# lf.net
KiCad netlist of a schematic drawn in EAGLE
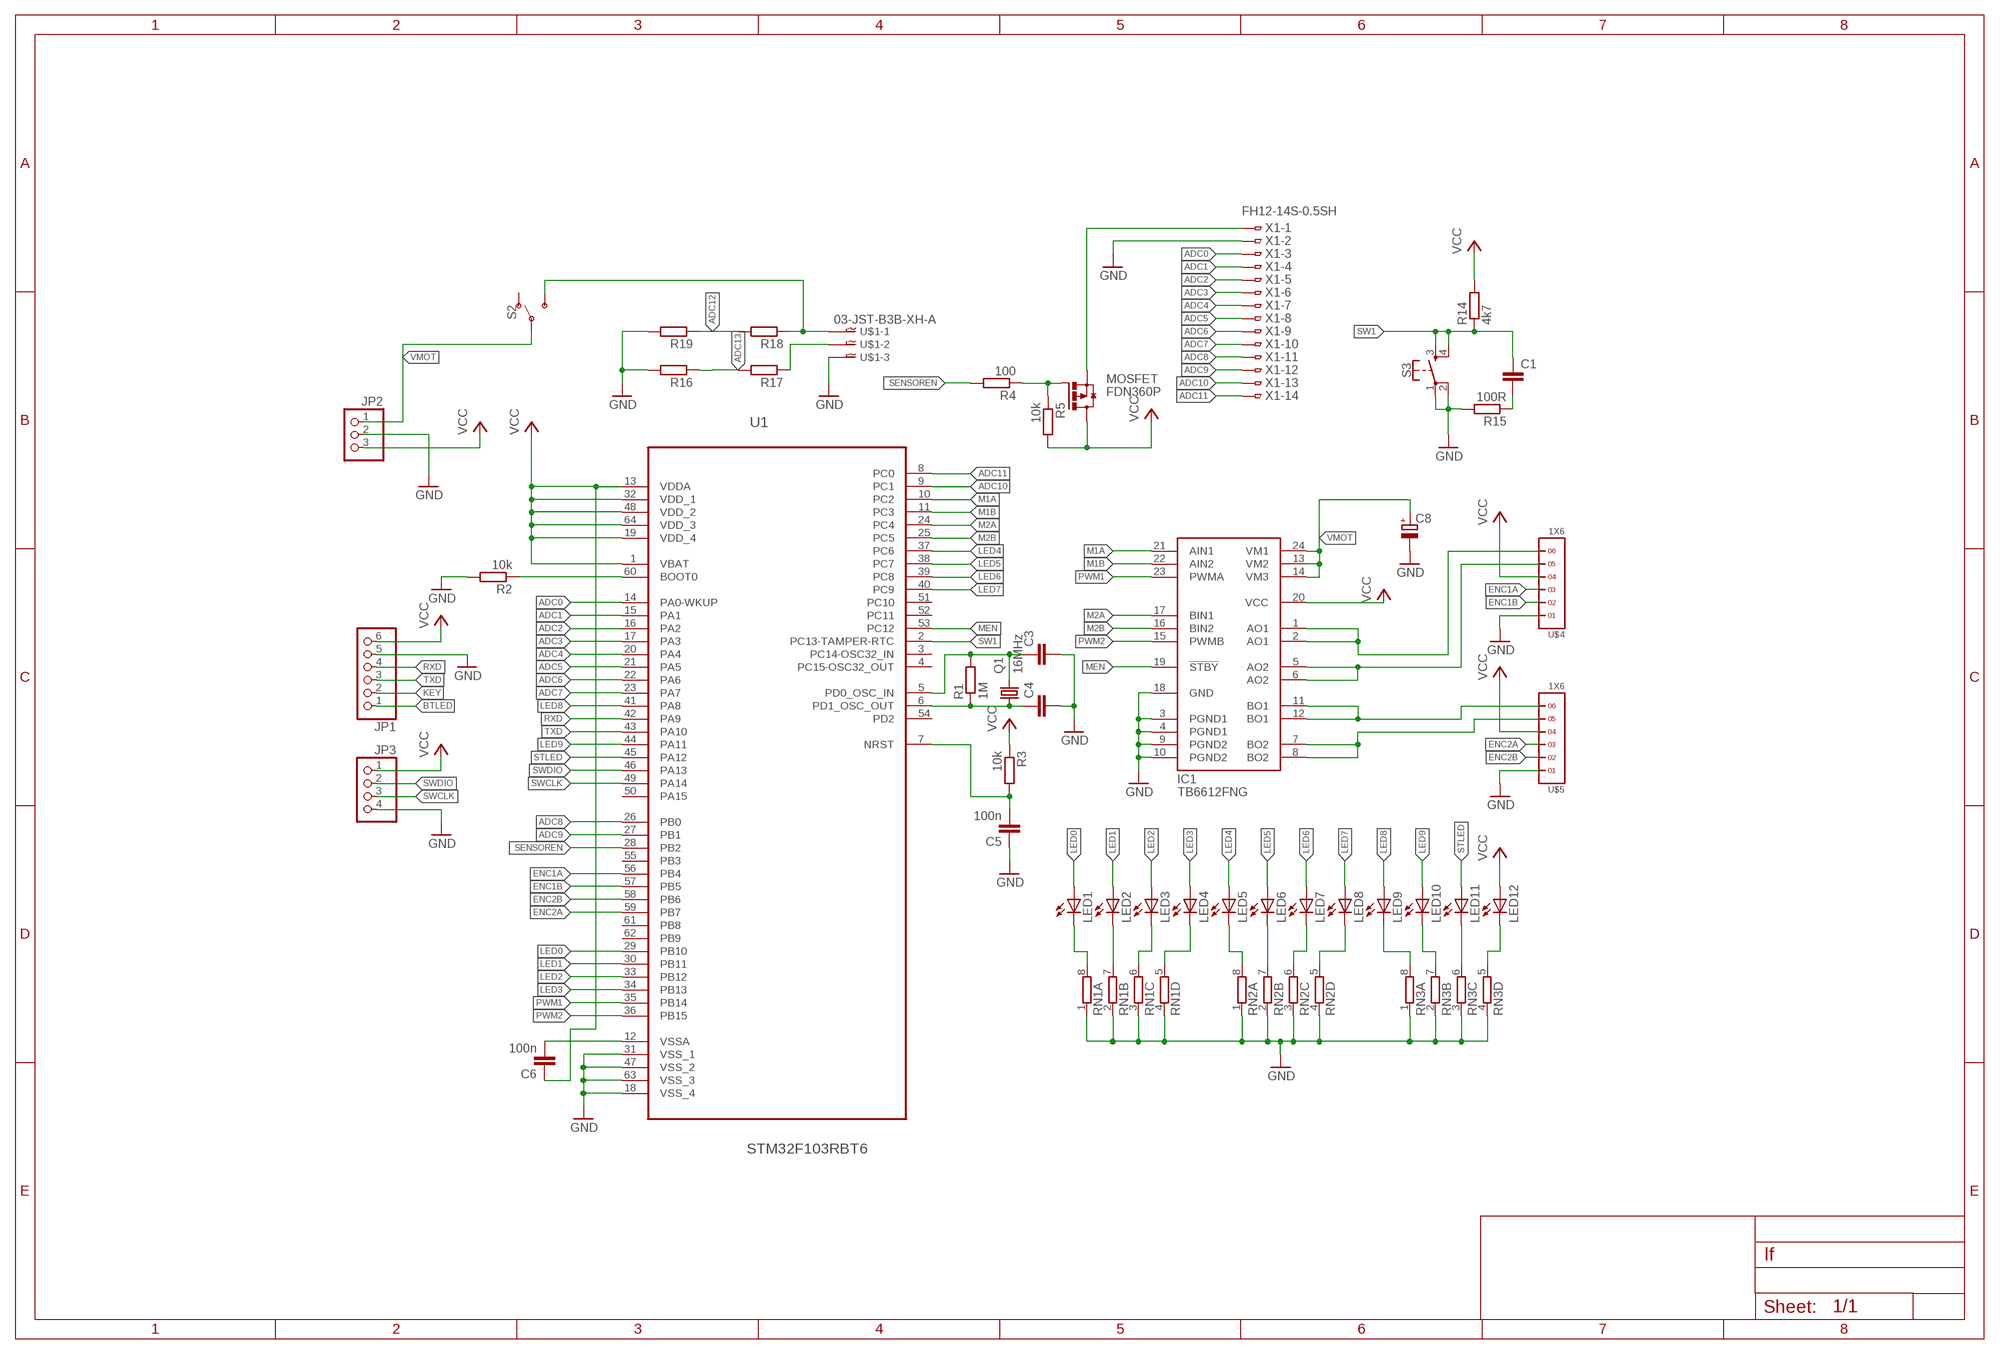
[diagram p0: schematic, sheet 1]

(export (version "E")
  (design (tool "Eeschema 10.0.6"))
  (components
    (comp (ref "C1")
      (value "C-EUC0603K")
      (footprint "eagle-import:C0603K")
      (libsource (lib "eagle-import") (part "C-EUC0603K"))
    )
    (comp (ref "C3")
      (value "C-EUC0603K")
      (footprint "eagle-import:C0603K")
      (libsource (lib "eagle-import") (part "C-EUC0603K"))
    )
    (comp (ref "C4")
      (value "C-EUC0603K")
      (footprint "eagle-import:C0603K")
      (libsource (lib "eagle-import") (part "C-EUC0603K"))
    )
    (comp (ref "C5")
      (value "100n")
      (footprint "eagle-import:C0603K")
      (libsource (lib "eagle-import") (part "C-EUC0603K"))
    )
    (comp (ref "C6")
      (value "100n")
      (footprint "eagle-import:C0603K")
      (libsource (lib "eagle-import") (part "C-EUC0603K"))
    )
    (comp (ref "C8")
      (value "CPOL-EUC/6032-28R")
      (footprint "eagle-import:C_6032-28R")
      (libsource (lib "eagle-import") (part "CPOL-EUC/6032-28R"))
    )
    (comp (ref "IC1")
      (value "TB6612FNG")
      (footprint "eagle-import:SSOP24")
      (libsource (lib "eagle-import") (part "TB6612FNG"))
    )
    (comp (ref "JP1")
      (value "PINHD-1X6")
      (footprint "eagle-import:1X06")
      (libsource (lib "eagle-import") (part "PINHD-1X6"))
    )
    (comp (ref "JP2")
      (value "PINHD-1X3")
      (footprint "eagle-import:1X03")
      (libsource (lib "eagle-import") (part "PINHD-1X3"))
    )
    (comp (ref "JP3")
      (value "PINHD-1X4")
      (footprint "eagle-import:1X04")
      (libsource (lib "eagle-import") (part "PINHD-1X4"))
    )
    (comp (ref "LED1")
      (value "LEDCHIPLED_0603")
      (footprint "eagle-import:CHIPLED_0603")
      (libsource (lib "eagle-import") (part "LEDCHIPLED_0603"))
    )
    (comp (ref "LED2")
      (value "LEDCHIPLED_0603")
      (footprint "eagle-import:CHIPLED_0603")
      (libsource (lib "eagle-import") (part "LEDCHIPLED_0603"))
    )
    (comp (ref "LED3")
      (value "LEDCHIPLED_0603")
      (footprint "eagle-import:CHIPLED_0603")
      (libsource (lib "eagle-import") (part "LEDCHIPLED_0603"))
    )
    (comp (ref "LED4")
      (value "LEDCHIPLED_0603")
      (footprint "eagle-import:CHIPLED_0603")
      (libsource (lib "eagle-import") (part "LEDCHIPLED_0603"))
    )
    (comp (ref "LED5")
      (value "LEDCHIPLED_0603")
      (footprint "eagle-import:CHIPLED_0603")
      (libsource (lib "eagle-import") (part "LEDCHIPLED_0603"))
    )
    (comp (ref "LED6")
      (value "LEDCHIPLED_0603")
      (footprint "eagle-import:CHIPLED_0603")
      (libsource (lib "eagle-import") (part "LEDCHIPLED_0603"))
    )
    (comp (ref "LED7")
      (value "LEDCHIPLED_0603")
      (footprint "eagle-import:CHIPLED_0603")
      (libsource (lib "eagle-import") (part "LEDCHIPLED_0603"))
    )
    (comp (ref "LED8")
      (value "LEDCHIPLED_0603")
      (footprint "eagle-import:CHIPLED_0603")
      (libsource (lib "eagle-import") (part "LEDCHIPLED_0603"))
    )
    (comp (ref "LED9")
      (value "LEDCHIPLED_0603")
      (footprint "eagle-import:CHIPLED_0603")
      (libsource (lib "eagle-import") (part "LEDCHIPLED_0603"))
    )
    (comp (ref "LED10")
      (value "LEDCHIPLED_0603")
      (footprint "eagle-import:CHIPLED_0603")
      (libsource (lib "eagle-import") (part "LEDCHIPLED_0603"))
    )
    (comp (ref "LED11")
      (value "LEDCHIPLED_0603")
      (footprint "eagle-import:CHIPLED_0603")
      (libsource (lib "eagle-import") (part "LEDCHIPLED_0603"))
    )
    (comp (ref "LED12")
      (value "LEDCHIPLED_0603")
      (footprint "eagle-import:CHIPLED_0603")
      (libsource (lib "eagle-import") (part "LEDCHIPLED_0603"))
    )
    (comp (ref "MOSFET")
      (value "FDN360P")
      (footprint "eagle-import:SUPER-SOT3")
      (libsource (lib "eagle-import") (part "FDN360P"))
    )
    (comp (ref "Q1")
      (value "16MHz")
      (footprint "eagle-import:3.2X2.5_KX-7")
      (libsource (lib "eagle-import") (part "KX-7"))
    )
    (comp (ref "R1")
      (value "1M")
      (footprint "eagle-import:R0603")
      (libsource (lib "eagle-import") (part "R-EU_R0603"))
    )
    (comp (ref "R2")
      (value "10k")
      (footprint "eagle-import:R0603")
      (libsource (lib "eagle-import") (part "R-EU_R0603"))
    )
    (comp (ref "R3")
      (value "10k")
      (footprint "eagle-import:R0603")
      (libsource (lib "eagle-import") (part "R-EU_R0603"))
    )
    (comp (ref "R4")
      (value "100")
      (footprint "eagle-import:R0603")
      (libsource (lib "eagle-import") (part "R-EU_R0603"))
    )
    (comp (ref "R5")
      (value "10k")
      (footprint "eagle-import:R0603")
      (libsource (lib "eagle-import") (part "R-EU_R0603"))
    )
    (comp (ref "R14")
      (value "4k7")
      (footprint "eagle-import:R0603")
      (libsource (lib "eagle-import") (part "R-EU_R0603"))
    )
    (comp (ref "R15")
      (value "100R")
      (footprint "eagle-import:R0603")
      (libsource (lib "eagle-import") (part "R-EU_R0603"))
    )
    (comp (ref "R16")
      (value "R-EU_R0603")
      (footprint "eagle-import:R0603")
      (libsource (lib "eagle-import") (part "R-EU_R0603"))
    )
    (comp (ref "R17")
      (value "R-EU_R0603")
      (footprint "eagle-import:R0603")
      (libsource (lib "eagle-import") (part "R-EU_R0603"))
    )
    (comp (ref "R18")
      (value "R-EU_R0603")
      (footprint "eagle-import:R0603")
      (libsource (lib "eagle-import") (part "R-EU_R0603"))
    )
    (comp (ref "R19")
      (value "R-EU_R0603")
      (footprint "eagle-import:R0603")
      (libsource (lib "eagle-import") (part "R-EU_R0603"))
    )
    (comp (ref "RN1")
      (value "4R-NEXB28V")
      (footprint "eagle-import:EXB28V")
      (libsource (lib "eagle-import") (part "4R-NEXB28V"))
    )
    (comp (ref "RN2")
      (value "4R-NEXB28V")
      (footprint "eagle-import:EXB28V")
      (libsource (lib "eagle-import") (part "4R-NEXB28V"))
    )
    (comp (ref "RN3")
      (value "4R-NEXB28V")
      (footprint "eagle-import:EXB28V")
      (libsource (lib "eagle-import") (part "4R-NEXB28V"))
    )
    (comp (ref "S2")
      (value "SWITCH-SPDT-PTH-11.6X4.0MM")
      (footprint "eagle-import:SWITCH_SPDT_PTH_11.6X4.0MM")
      (libsource (lib "eagle-import") (part "SWITCH-SPDT-PTH-11.6X4.0MM"))
    )
    (comp (ref "S3")
      (value "MOMENTARY-SWITCH-SPST-2-SMD-5.2MM")
      (footprint "eagle-import:TACTILE_SWITCH_SMD_5.2MM")
      (libsource (lib "eagle-import") (part "MOMENTARY-SWITCH-SPST-2-SMD-5.2MM"))
    )
    (comp (ref "U$1")
      (value "03-JST-B3B-XH-A")
      (footprint "eagle-import:B3B-XH")
      (libsource (lib "eagle-import") (part "03-JST-B3B-XH-A"))
    )
    (comp (ref "U$4")
      (value "1X6")
      (footprint "eagle-import:1X6")
      (libsource (lib "eagle-import") (part "1X6"))
    )
    (comp (ref "U$5")
      (value "1X6")
      (footprint "eagle-import:1X6")
      (libsource (lib "eagle-import") (part "1X6"))
    )
    (comp (ref "U1")
      (value "STM32F103RBT6")
      (footprint "eagle-import:QFP50P1200X1200X160-64N")
      (fields (field (name "MF") "STMicroelectronics"))
      (libsource (lib "eagle-import") (part "STM32F103RBT6"))
    )
    (comp (ref "X1")
      (value "FH12-14S-0.5SH")
      (footprint "eagle-import:FH12-14S-0.5SH")
      (fields (field (name "MPN") "MC34827"))
      (libsource (lib "eagle-import") (part "FH12-14S-0.5SH"))
    )
  )
  (nets
    (net (code "1") (name "ADC0") (class "Default")
      (node (ref "U1") (pin "14") (pinfunction "PA0-WKUP_14") (pintype "bidirectional"))
      (node (ref "X1") (pin "3") (pinfunction "1_3") (pintype "passive"))
    )
    (net (code "2") (name "ADC1") (class "Default")
      (node (ref "U1") (pin "15") (pinfunction "PA1_15") (pintype "bidirectional"))
      (node (ref "X1") (pin "4") (pinfunction "1_4") (pintype "passive"))
    )
    (net (code "3") (name "ADC2") (class "Default")
      (node (ref "U1") (pin "16") (pinfunction "PA2_16") (pintype "bidirectional"))
      (node (ref "X1") (pin "5") (pinfunction "1_5") (pintype "passive"))
    )
    (net (code "4") (name "ADC3") (class "Default")
      (node (ref "U1") (pin "17") (pinfunction "PA3_17") (pintype "bidirectional"))
      (node (ref "X1") (pin "6") (pinfunction "1_6") (pintype "passive"))
    )
    (net (code "5") (name "ADC4") (class "Default")
      (node (ref "U1") (pin "20") (pinfunction "PA4_20") (pintype "bidirectional"))
      (node (ref "X1") (pin "7") (pinfunction "1_7") (pintype "passive"))
    )
    (net (code "6") (name "ADC5") (class "Default")
      (node (ref "U1") (pin "21") (pinfunction "PA5_21") (pintype "bidirectional"))
      (node (ref "X1") (pin "8") (pinfunction "1_8") (pintype "passive"))
    )
    (net (code "7") (name "ADC6") (class "Default")
      (node (ref "U1") (pin "22") (pinfunction "PA6_22") (pintype "bidirectional"))
      (node (ref "X1") (pin "9") (pinfunction "1_9") (pintype "passive"))
    )
    (net (code "8") (name "ADC7") (class "Default")
      (node (ref "U1") (pin "23") (pinfunction "PA7_23") (pintype "bidirectional"))
      (node (ref "X1") (pin "10") (pinfunction "1_10") (pintype "passive"))
    )
    (net (code "9") (name "ADC8") (class "Default")
      (node (ref "U1") (pin "26") (pinfunction "PB0_26") (pintype "bidirectional"))
      (node (ref "X1") (pin "11") (pinfunction "1_11") (pintype "passive"))
    )
    (net (code "10") (name "ADC9") (class "Default")
      (node (ref "U1") (pin "27") (pinfunction "PB1_27") (pintype "bidirectional"))
      (node (ref "X1") (pin "12") (pinfunction "1_12") (pintype "passive"))
    )
    (net (code "11") (name "ADC10") (class "Default")
      (node (ref "U1") (pin "9") (pinfunction "PC1_9") (pintype "bidirectional"))
      (node (ref "X1") (pin "13") (pinfunction "1_13") (pintype "passive"))
    )
    (net (code "12") (name "ADC11") (class "Default")
      (node (ref "U1") (pin "8") (pinfunction "PC0_8") (pintype "bidirectional"))
      (node (ref "X1") (pin "14") (pinfunction "1_14") (pintype "passive"))
    )
    (net (code "13") (name "ADC12") (class "Default")
      (node (ref "R18") (pin "2") (pinfunction "2_2") (pintype "passive"))
      (node (ref "R19") (pin "1") (pinfunction "1_1") (pintype "passive"))
    )
    (net (code "14") (name "ADC13") (class "Default")
      (node (ref "R16") (pin "1") (pinfunction "1_1") (pintype "passive"))
      (node (ref "R17") (pin "2") (pinfunction "2_2") (pintype "passive"))
    )
    (net (code "15") (name "BTLED") (class "Default")
      (node (ref "JP1") (pin "1") (pinfunction "1_1") (pintype "passive"))
    )
    (net (code "16") (name "ENC1A") (class "Default")
      (node (ref "U$4") (pin "3") (pinfunction "3_3") (pintype "bidirectional"))
      (node (ref "U1") (pin "56") (pinfunction "PB4_56") (pintype "bidirectional"))
    )
    (net (code "17") (name "ENC1B") (class "Default")
      (node (ref "U$4") (pin "2") (pinfunction "2_2") (pintype "bidirectional"))
      (node (ref "U1") (pin "57") (pinfunction "PB5_57") (pintype "bidirectional"))
    )
    (net (code "18") (name "ENC2A") (class "Default")
      (node (ref "U$5") (pin "3") (pinfunction "3_3") (pintype "bidirectional"))
      (node (ref "U1") (pin "59") (pinfunction "PB7_59") (pintype "bidirectional"))
    )
    (net (code "19") (name "ENC2B") (class "Default")
      (node (ref "U$5") (pin "2") (pinfunction "2_2") (pintype "bidirectional"))
      (node (ref "U1") (pin "58") (pinfunction "PB6_58") (pintype "bidirectional"))
    )
    (net (code "20") (name "GND") (class "Default")
      (node (ref "C3") (pin "2") (pinfunction "2_2") (pintype "passive"))
      (node (ref "C4") (pin "2") (pinfunction "2_2") (pintype "passive"))
      (node (ref "C5") (pin "1") (pinfunction "1_1") (pintype "passive"))
      (node (ref "C8") (pin "-") (pinfunction "-_-") (pintype "passive"))
      (node (ref "IC1") (pin "10") (pinfunction "PGND2_10") (pintype "bidirectional"))
      (node (ref "IC1") (pin "18") (pinfunction "GND_18") (pintype "bidirectional"))
      (node (ref "IC1") (pin "3") (pinfunction "PGND1_3") (pintype "bidirectional"))
      (node (ref "IC1") (pin "4") (pinfunction "PGND1_4") (pintype "bidirectional"))
      (node (ref "IC1") (pin "9") (pinfunction "PGND2_9") (pintype "bidirectional"))
      (node (ref "JP1") (pin "5") (pinfunction "5_5") (pintype "passive"))
      (node (ref "JP2") (pin "2") (pinfunction "2_2") (pintype "passive"))
      (node (ref "JP3") (pin "4") (pinfunction "4_4") (pintype "passive"))
      (node (ref "R15") (pin "2") (pinfunction "2_2") (pintype "passive"))
      (node (ref "R16") (pin "2") (pinfunction "2_2") (pintype "passive"))
      (node (ref "R19") (pin "2") (pinfunction "2_2") (pintype "passive"))
      (node (ref "R2") (pin "2") (pinfunction "2_2") (pintype "passive"))
      (node (ref "RN1") (pin "1") (pinfunction "1_1") (pintype "passive"))
      (node (ref "RN1") (pin "2") (pinfunction "1_2") (pintype "passive"))
      (node (ref "RN1") (pin "3") (pinfunction "1_3") (pintype "passive"))
      (node (ref "RN1") (pin "4") (pinfunction "1_4") (pintype "passive"))
      (node (ref "RN2") (pin "1") (pinfunction "1_1") (pintype "passive"))
      (node (ref "RN2") (pin "2") (pinfunction "1_2") (pintype "passive"))
      (node (ref "RN2") (pin "3") (pinfunction "1_3") (pintype "passive"))
      (node (ref "RN2") (pin "4") (pinfunction "1_4") (pintype "passive"))
      (node (ref "RN3") (pin "1") (pinfunction "1_1") (pintype "passive"))
      (node (ref "RN3") (pin "2") (pinfunction "1_2") (pintype "passive"))
      (node (ref "RN3") (pin "3") (pinfunction "1_3") (pintype "passive"))
      (node (ref "RN3") (pin "4") (pinfunction "1_4") (pintype "passive"))
      (node (ref "S3") (pin "1") (pinfunction "1_1") (pintype "passive"))
      (node (ref "S3") (pin "2") (pinfunction "2_2") (pintype "passive"))
      (node (ref "U$1") (pin "P$3") (pinfunction "1_P$3") (pintype "passive"))
      (node (ref "U$4") (pin "1") (pinfunction "1_1") (pintype "bidirectional"))
      (node (ref "U$5") (pin "1") (pinfunction "1_1") (pintype "bidirectional"))
      (node (ref "U1") (pin "18") (pinfunction "VSS_4_18") (pintype "passive"))
      (node (ref "U1") (pin "31") (pinfunction "VSS_1_31") (pintype "passive"))
      (node (ref "U1") (pin "47") (pinfunction "VSS_2_47") (pintype "passive"))
      (node (ref "U1") (pin "63") (pinfunction "VSS_3_63") (pintype "passive"))
      (node (ref "X1") (pin "2") (pinfunction "1_2") (pintype "passive"))
    )
    (net (code "21") (name "KEY") (class "Default")
      (node (ref "JP1") (pin "2") (pinfunction "2_2") (pintype "passive"))
    )
    (net (code "22") (name "LED0") (class "Default")
      (node (ref "LED1") (pin "A") (pinfunction "A_A") (pintype "passive"))
      (node (ref "U1") (pin "29") (pinfunction "PB10_29") (pintype "bidirectional"))
    )
    (net (code "23") (name "LED1") (class "Default")
      (node (ref "LED2") (pin "A") (pinfunction "A_A") (pintype "passive"))
      (node (ref "U1") (pin "30") (pinfunction "PB11_30") (pintype "bidirectional"))
    )
    (net (code "24") (name "LED2") (class "Default")
      (node (ref "LED3") (pin "A") (pinfunction "A_A") (pintype "passive"))
      (node (ref "U1") (pin "33") (pinfunction "PB12_33") (pintype "bidirectional"))
    )
    (net (code "25") (name "LED3") (class "Default")
      (node (ref "LED4") (pin "A") (pinfunction "A_A") (pintype "passive"))
      (node (ref "U1") (pin "34") (pinfunction "PB13_34") (pintype "bidirectional"))
    )
    (net (code "26") (name "LED4") (class "Default")
      (node (ref "LED5") (pin "A") (pinfunction "A_A") (pintype "passive"))
      (node (ref "U1") (pin "37") (pinfunction "PC6_37") (pintype "bidirectional"))
    )
    (net (code "27") (name "LED5") (class "Default")
      (node (ref "LED6") (pin "A") (pinfunction "A_A") (pintype "passive"))
      (node (ref "U1") (pin "38") (pinfunction "PC7_38") (pintype "bidirectional"))
    )
    (net (code "28") (name "LED6") (class "Default")
      (node (ref "LED7") (pin "A") (pinfunction "A_A") (pintype "passive"))
      (node (ref "U1") (pin "39") (pinfunction "PC8_39") (pintype "bidirectional"))
    )
    (net (code "29") (name "LED7") (class "Default")
      (node (ref "LED8") (pin "A") (pinfunction "A_A") (pintype "passive"))
      (node (ref "U1") (pin "40") (pinfunction "PC9_40") (pintype "bidirectional"))
    )
    (net (code "30") (name "LED8") (class "Default")
      (node (ref "LED9") (pin "A") (pinfunction "A_A") (pintype "passive"))
      (node (ref "U1") (pin "41") (pinfunction "PA8_41") (pintype "bidirectional"))
    )
    (net (code "31") (name "LED9") (class "Default")
      (node (ref "LED10") (pin "A") (pinfunction "A_A") (pintype "passive"))
      (node (ref "U1") (pin "44") (pinfunction "PA11_44") (pintype "bidirectional"))
    )
    (net (code "32") (name "M1A") (class "Default")
      (node (ref "IC1") (pin "21") (pinfunction "AIN1_21") (pintype "bidirectional"))
      (node (ref "U1") (pin "10") (pinfunction "PC2_10") (pintype "bidirectional"))
    )
    (net (code "33") (name "M1B") (class "Default")
      (node (ref "IC1") (pin "22") (pinfunction "AIN2_22") (pintype "bidirectional"))
      (node (ref "U1") (pin "11") (pinfunction "PC3_11") (pintype "bidirectional"))
    )
    (net (code "34") (name "M2A") (class "Default")
      (node (ref "IC1") (pin "17") (pinfunction "BIN1_17") (pintype "bidirectional"))
      (node (ref "U1") (pin "24") (pinfunction "PC4_24") (pintype "bidirectional"))
    )
    (net (code "35") (name "M2B") (class "Default")
      (node (ref "IC1") (pin "16") (pinfunction "BIN2_16") (pintype "bidirectional"))
      (node (ref "U1") (pin "25") (pinfunction "PC5_25") (pintype "bidirectional"))
    )
    (net (code "36") (name "MEN") (class "Default")
      (node (ref "IC1") (pin "19") (pinfunction "~{STBY}_19") (pintype "bidirectional"))
      (node (ref "U1") (pin "53") (pinfunction "PC12_53") (pintype "bidirectional"))
    )
    (net (code "37") (name "Net-(C1-Pad2)") (class "Default")
      (node (ref "C1") (pin "2") (pinfunction "2_2") (pintype "passive"))
      (node (ref "R15") (pin "1") (pinfunction "1_1") (pintype "passive"))
    )
    (net (code "38") (name "Net-(IC1-AO1-Pad1)") (class "Default")
      (node (ref "IC1") (pin "1") (pinfunction "AO1_1") (pintype "bidirectional"))
      (node (ref "IC1") (pin "2") (pinfunction "AO1_2") (pintype "bidirectional"))
      (node (ref "U$4") (pin "6") (pinfunction "6_6") (pintype "bidirectional"))
    )
    (net (code "39") (name "Net-(IC1-AO2-Pad5)") (class "Default")
      (node (ref "IC1") (pin "5") (pinfunction "AO2_5") (pintype "bidirectional"))
      (node (ref "IC1") (pin "6") (pinfunction "AO2_6") (pintype "bidirectional"))
      (node (ref "U$4") (pin "5") (pinfunction "5_5") (pintype "bidirectional"))
    )
    (net (code "40") (name "Net-(IC1-BO1-Pad11)") (class "Default")
      (node (ref "IC1") (pin "11") (pinfunction "BO1_11") (pintype "bidirectional"))
      (node (ref "IC1") (pin "12") (pinfunction "BO1_12") (pintype "bidirectional"))
      (node (ref "U$5") (pin "6") (pinfunction "6_6") (pintype "bidirectional"))
    )
    (net (code "41") (name "Net-(IC1-BO2-Pad7)") (class "Default")
      (node (ref "IC1") (pin "7") (pinfunction "BO2_7") (pintype "bidirectional"))
      (node (ref "IC1") (pin "8") (pinfunction "BO2_8") (pintype "bidirectional"))
      (node (ref "U$5") (pin "5") (pinfunction "5_5") (pintype "bidirectional"))
    )
    (net (code "42") (name "Net-(MOSFET-G)") (class "Default")
      (node (ref "MOSFET") (pin "1") (pinfunction "G_1") (pintype "passive"))
      (node (ref "R4") (pin "1") (pinfunction "1_1") (pintype "passive"))
      (node (ref "R5") (pin "1") (pinfunction "1_1") (pintype "passive"))
    )
    (net (code "43") (name "Net-(MOSFET-S)") (class "Default")
      (node (ref "MOSFET") (pin "2") (pinfunction "S_2") (pintype "passive"))
      (node (ref "X1") (pin "1") (pinfunction "1_1") (pintype "passive"))
    )
    (net (code "44") (name "Net-(Q1-2)") (class "Default")
      (node (ref "C3") (pin "1") (pinfunction "1_1") (pintype "passive"))
      (node (ref "Q1") (pin "3") (pinfunction "2_3") (pintype "passive"))
      (node (ref "R1") (pin "2") (pinfunction "2_2") (pintype "passive"))
      (node (ref "U1") (pin "5") (pinfunction "PD0_OSC_IN_5") (pintype "bidirectional"))
    )
    (net (code "45") (name "Net-(RN1A-2)") (class "Default")
      (node (ref "LED1") (pin "C") (pinfunction "C_C") (pintype "passive"))
      (node (ref "RN1") (pin "8") (pinfunction "2_8") (pintype "passive"))
    )
    (net (code "46") (name "Net-(RN1B-2)") (class "Default")
      (node (ref "LED2") (pin "C") (pinfunction "C_C") (pintype "passive"))
      (node (ref "RN1") (pin "7") (pinfunction "2_7") (pintype "passive"))
    )
    (net (code "47") (name "Net-(RN1C-2)") (class "Default")
      (node (ref "LED3") (pin "C") (pinfunction "C_C") (pintype "passive"))
      (node (ref "RN1") (pin "6") (pinfunction "2_6") (pintype "passive"))
    )
    (net (code "48") (name "Net-(RN1D-2)") (class "Default")
      (node (ref "LED4") (pin "C") (pinfunction "C_C") (pintype "passive"))
      (node (ref "RN1") (pin "5") (pinfunction "2_5") (pintype "passive"))
    )
    (net (code "49") (name "Net-(RN2A-2)") (class "Default")
      (node (ref "LED5") (pin "C") (pinfunction "C_C") (pintype "passive"))
      (node (ref "RN2") (pin "8") (pinfunction "2_8") (pintype "passive"))
    )
    (net (code "50") (name "Net-(RN2B-2)") (class "Default")
      (node (ref "LED6") (pin "C") (pinfunction "C_C") (pintype "passive"))
      (node (ref "RN2") (pin "7") (pinfunction "2_7") (pintype "passive"))
    )
    (net (code "51") (name "Net-(RN2C-2)") (class "Default")
      (node (ref "LED7") (pin "C") (pinfunction "C_C") (pintype "passive"))
      (node (ref "RN2") (pin "6") (pinfunction "2_6") (pintype "passive"))
    )
    (net (code "52") (name "Net-(RN2D-2)") (class "Default")
      (node (ref "LED8") (pin "C") (pinfunction "C_C") (pintype "passive"))
      (node (ref "RN2") (pin "5") (pinfunction "2_5") (pintype "passive"))
    )
    (net (code "53") (name "Net-(RN3A-2)") (class "Default")
      (node (ref "LED9") (pin "C") (pinfunction "C_C") (pintype "passive"))
      (node (ref "RN3") (pin "8") (pinfunction "2_8") (pintype "passive"))
    )
    (net (code "54") (name "Net-(RN3B-2)") (class "Default")
      (node (ref "LED10") (pin "C") (pinfunction "C_C") (pintype "passive"))
      (node (ref "RN3") (pin "7") (pinfunction "2_7") (pintype "passive"))
    )
    (net (code "55") (name "Net-(RN3C-2)") (class "Default")
      (node (ref "LED11") (pin "C") (pinfunction "C_C") (pintype "passive"))
      (node (ref "RN3") (pin "6") (pinfunction "2_6") (pintype "passive"))
    )
    (net (code "56") (name "Net-(RN3D-2)") (class "Default")
      (node (ref "LED12") (pin "C") (pinfunction "C_C") (pintype "passive"))
      (node (ref "RN3") (pin "5") (pinfunction "2_5") (pintype "passive"))
    )
    (net (code "57") (name "Net-(S2-S)") (class "Default")
      (node (ref "R18") (pin "1") (pinfunction "1_1") (pintype "passive"))
      (node (ref "S2") (pin "3") (pinfunction "S_3") (pintype "passive"))
      (node (ref "U$1") (pin "P$1") (pinfunction "1_P$1") (pintype "passive"))
    )
    (net (code "58") (name "Net-(U$1B-1)") (class "Default")
      (node (ref "R17") (pin "1") (pinfunction "1_1") (pintype "passive"))
      (node (ref "U$1") (pin "P$2") (pinfunction "1_P$2") (pintype "passive"))
    )
    (net (code "59") (name "Net-(U1-BOOT0)") (class "Default")
      (node (ref "R2") (pin "1") (pinfunction "1_1") (pintype "passive"))
      (node (ref "U1") (pin "60") (pinfunction "BOOT0_60") (pintype "input"))
    )
    (net (code "60") (name "Net-(U1-NRST)") (class "Default")
      (node (ref "C5") (pin "2") (pinfunction "2_2") (pintype "passive"))
      (node (ref "R3") (pin "2") (pinfunction "2_2") (pintype "passive"))
      (node (ref "U1") (pin "7") (pinfunction "NRST_7") (pintype "bidirectional"))
    )
    (net (code "61") (name "Net-(U1-PD1_OSC_OUT)") (class "Default")
      (node (ref "C4") (pin "1") (pinfunction "1_1") (pintype "passive"))
      (node (ref "Q1") (pin "1") (pinfunction "1_1") (pintype "passive"))
      (node (ref "R1") (pin "1") (pinfunction "1_1") (pintype "passive"))
      (node (ref "U1") (pin "6") (pinfunction "PD1_OSC_OUT_6") (pintype "bidirectional"))
    )
    (net (code "62") (name "Net-(U1-VSSA)") (class "Default")
      (node (ref "C6") (pin "2") (pinfunction "2_2") (pintype "passive"))
      (node (ref "U1") (pin "12") (pinfunction "VSSA_12") (pintype "passive"))
    )
    (net (code "63") (name "PWM1") (class "Default")
      (node (ref "IC1") (pin "23") (pinfunction "PWMA_23") (pintype "bidirectional"))
      (node (ref "U1") (pin "35") (pinfunction "PB14_35") (pintype "bidirectional"))
    )
    (net (code "64") (name "PWM2") (class "Default")
      (node (ref "IC1") (pin "15") (pinfunction "PWMB_15") (pintype "bidirectional"))
      (node (ref "U1") (pin "36") (pinfunction "PB15_36") (pintype "bidirectional"))
    )
    (net (code "65") (name "RXD") (class "Default")
      (node (ref "JP1") (pin "4") (pinfunction "4_4") (pintype "passive"))
      (node (ref "U1") (pin "42") (pinfunction "PA9_42") (pintype "bidirectional"))
    )
    (net (code "66") (name "SENSOREN") (class "Default")
      (node (ref "R4") (pin "2") (pinfunction "2_2") (pintype "passive"))
      (node (ref "U1") (pin "28") (pinfunction "PB2_28") (pintype "bidirectional"))
    )
    (net (code "67") (name "STLED") (class "Default")
      (node (ref "LED11") (pin "A") (pinfunction "A_A") (pintype "passive"))
      (node (ref "U1") (pin "45") (pinfunction "PA12_45") (pintype "bidirectional"))
    )
    (net (code "68") (name "SW1") (class "Default")
      (node (ref "C1") (pin "1") (pinfunction "1_1") (pintype "passive"))
      (node (ref "R14") (pin "1") (pinfunction "1_1") (pintype "passive"))
      (node (ref "S3") (pin "3") (pinfunction "3_3") (pintype "passive"))
      (node (ref "S3") (pin "4") (pinfunction "4_4") (pintype "passive"))
      (node (ref "U1") (pin "2") (pinfunction "PC13-TAMPER-RTC_2") (pintype "bidirectional"))
    )
    (net (code "69") (name "SWCLK") (class "Default")
      (node (ref "JP3") (pin "3") (pinfunction "3_3") (pintype "passive"))
      (node (ref "U1") (pin "49") (pinfunction "PA14_49") (pintype "bidirectional"))
    )
    (net (code "70") (name "SWDIO") (class "Default")
      (node (ref "JP3") (pin "2") (pinfunction "2_2") (pintype "passive"))
      (node (ref "U1") (pin "46") (pinfunction "PA13_46") (pintype "bidirectional"))
    )
    (net (code "71") (name "TXD") (class "Default")
      (node (ref "JP1") (pin "3") (pinfunction "3_3") (pintype "passive"))
      (node (ref "U1") (pin "43") (pinfunction "PA10_43") (pintype "bidirectional"))
    )
    (net (code "72") (name "VCC") (class "Default")
      (node (ref "C6") (pin "1") (pinfunction "1_1") (pintype "passive"))
      (node (ref "IC1") (pin "20") (pinfunction "VCC_20") (pintype "bidirectional"))
      (node (ref "JP1") (pin "6") (pinfunction "6_6") (pintype "passive"))
      (node (ref "JP2") (pin "3") (pinfunction "3_3") (pintype "passive"))
      (node (ref "JP3") (pin "1") (pinfunction "1_1") (pintype "passive"))
      (node (ref "LED12") (pin "A") (pinfunction "A_A") (pintype "passive"))
      (node (ref "MOSFET") (pin "3") (pinfunction "D_3") (pintype "passive"))
      (node (ref "R14") (pin "2") (pinfunction "2_2") (pintype "passive"))
      (node (ref "R3") (pin "1") (pinfunction "1_1") (pintype "passive"))
      (node (ref "R5") (pin "2") (pinfunction "2_2") (pintype "passive"))
      (node (ref "U$4") (pin "4") (pinfunction "4_4") (pintype "bidirectional"))
      (node (ref "U$5") (pin "4") (pinfunction "4_4") (pintype "bidirectional"))
      (node (ref "U1") (pin "1") (pinfunction "VBAT_1") (pintype "input"))
      (node (ref "U1") (pin "13") (pinfunction "VDDA_13") (pintype "power_in"))
      (node (ref "U1") (pin "19") (pinfunction "VDD_4_19") (pintype "power_in"))
      (node (ref "U1") (pin "32") (pinfunction "VDD_1_32") (pintype "power_in"))
      (node (ref "U1") (pin "48") (pinfunction "VDD_2_48") (pintype "power_in"))
      (node (ref "U1") (pin "64") (pinfunction "VDD_3_64") (pintype "power_in"))
    )
    (net (code "73") (name "VMOT") (class "Default")
      (node (ref "C8") (pin "+") (pinfunction "+_+") (pintype "passive"))
      (node (ref "IC1") (pin "13") (pinfunction "VM2_13") (pintype "bidirectional"))
      (node (ref "IC1") (pin "14") (pinfunction "VM3_14") (pintype "bidirectional"))
      (node (ref "IC1") (pin "24") (pinfunction "VM1_24") (pintype "bidirectional"))
      (node (ref "JP2") (pin "1") (pinfunction "1_1") (pintype "passive"))
      (node (ref "S2") (pin "2") (pinfunction "P_2") (pintype "passive"))
    )
    (net (code "74") (name "unconnected-(S2-O-Pad1)") (class "Default")
      (node (ref "S2") (pin "1") (pinfunction "O_1") (pintype "passive"))
    )
    (net (code "75") (name "unconnected-(U1-PA15-Pad50)") (class "Default")
      (node (ref "U1") (pin "50") (pinfunction "PA15_50") (pintype "bidirectional"))
    )
    (net (code "76") (name "unconnected-(U1-PB3-Pad55)") (class "Default")
      (node (ref "U1") (pin "55") (pinfunction "PB3_55") (pintype "bidirectional"))
    )
    (net (code "77") (name "unconnected-(U1-PB8-Pad61)") (class "Default")
      (node (ref "U1") (pin "61") (pinfunction "PB8_61") (pintype "bidirectional"))
    )
    (net (code "78") (name "unconnected-(U1-PB9-Pad62)") (class "Default")
      (node (ref "U1") (pin "62") (pinfunction "PB9_62") (pintype "bidirectional"))
    )
    (net (code "79") (name "unconnected-(U1-PC10-Pad51)") (class "Default")
      (node (ref "U1") (pin "51") (pinfunction "PC10_51") (pintype "bidirectional"))
    )
    (net (code "80") (name "unconnected-(U1-PC11-Pad52)") (class "Default")
      (node (ref "U1") (pin "52") (pinfunction "PC11_52") (pintype "bidirectional"))
    )
    (net (code "81") (name "unconnected-(U1-PC14-OSC32_IN-Pad3)") (class "Default")
      (node (ref "U1") (pin "3") (pinfunction "PC14-OSC32_IN_3") (pintype "bidirectional"))
    )
    (net (code "82") (name "unconnected-(U1-PC15-OSC32_OUT-Pad4)") (class "Default")
      (node (ref "U1") (pin "4") (pinfunction "PC15-OSC32_OUT_4") (pintype "bidirectional"))
    )
    (net (code "83") (name "unconnected-(U1-PD2-Pad54)") (class "Default")
      (node (ref "U1") (pin "54") (pinfunction "PD2_54") (pintype "bidirectional"))
    )
  )
)
